# Gate_Driver.net
KiCad netlist of a schematic drawn in Altium Designer
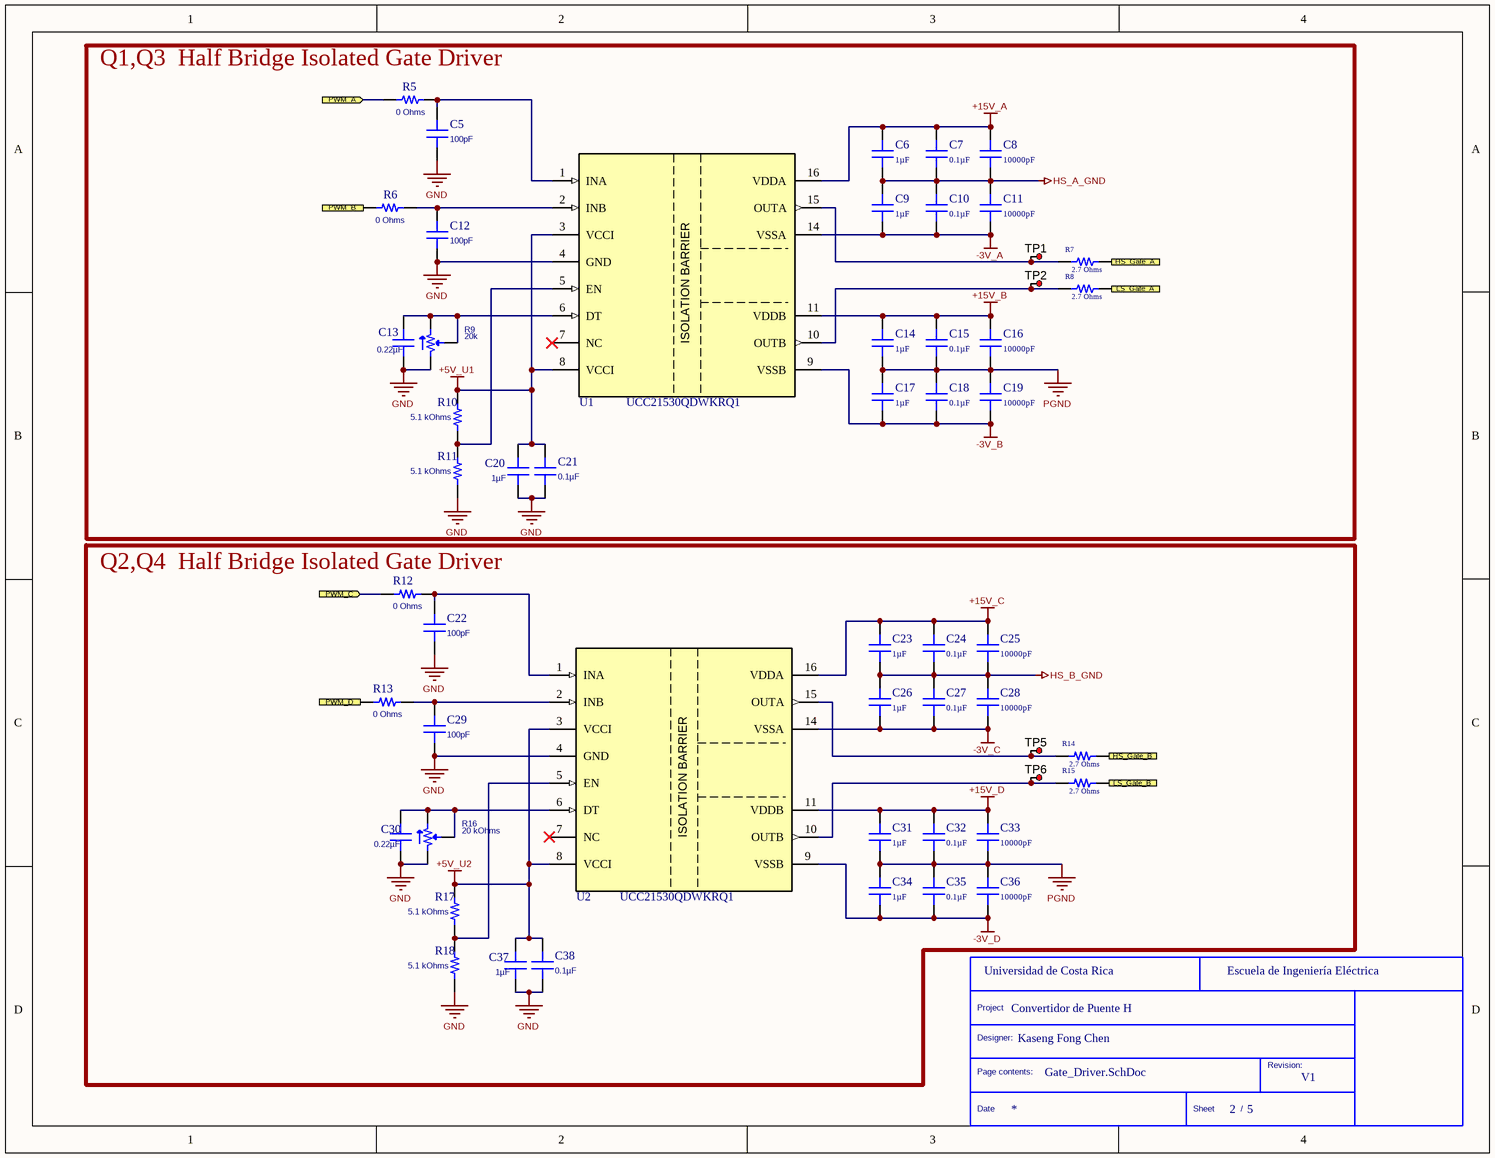
[diagram p0: Gate_Driver.SchDoc]

(export (version "E")
  (design (tool "Eeschema 10.0.6"))
  (components
    (comp (ref "C5")
      (value "100pF")
      (footprint "CAP 0603_1608")
      (description "CAP CER 100PF 100V C0G/NP0 0603")
      (fields
        (field (name "PART NUMBER") "GCM1885C2A101JA16D")
        (field (name "MANUFACTURER") "Murata Electronics")
      )
      (libsource (lib "Celestial Altium Library - altium_library") (part "Capacitor"))
    )
    (comp (ref "C6")
      (value "1µF")
      (footprint "CAP 0603_1608")
      (description "CAP CER 1UF 50V X7R 0603")
      (fields (field (name "PART NUMBER") "UMK107AB7105KA-T") (field (name "MANUFACTURER") "Taiyo Yuden"))
      (libsource (lib "Celestial Altium Library - altium_library") (part "Capacitor"))
    )
    (comp (ref "C7")
      (value "0.1µF")
      (footprint "CAP 0603_1608")
      (description "CAP CER 0.1UF 50V X7R 0603")
      (fields (field (name "PART NUMBER") "C0603C104M5RACTU") (field (name "MANUFACTURER") "KEMET"))
      (libsource (lib "Celestial Altium Library - altium_library") (part "Capacitor"))
    )
    (comp (ref "C8")
      (value "10000pF")
      (footprint "CAP 0603_1608")
      (description "CAP CER 10000PF 50V C0G 0603")
      (fields
        (field (name "PART NUMBER") "CGA3E2C0G1H103J080AA")
        (field (name "MANUFACTURER") "TDK Corporation")
      )
      (libsource (lib "Celestial Altium Library - altium_library") (part "Capacitor"))
    )
    (comp (ref "C9")
      (value "1µF")
      (footprint "CAP 0603_1608")
      (description "CAP CER 1UF 50V X7R 0603")
      (fields (field (name "PART NUMBER") "UMK107AB7105KA-T") (field (name "MANUFACTURER") "Taiyo Yuden"))
      (libsource (lib "Celestial Altium Library - altium_library") (part "Capacitor"))
    )
    (comp (ref "C10")
      (value "0.1µF")
      (footprint "CAP 0603_1608")
      (description "CAP CER 0.1UF 50V X7R 0603")
      (fields (field (name "PART NUMBER") "C0603C104M5RACTU") (field (name "MANUFACTURER") "KEMET"))
      (libsource (lib "Celestial Altium Library - altium_library") (part "Capacitor"))
    )
    (comp (ref "C11")
      (value "10000pF")
      (footprint "CAP 0603_1608")
      (description "CAP CER 10000PF 50V C0G 0603")
      (fields
        (field (name "PART NUMBER") "CGA3E2C0G1H103J080AA")
        (field (name "MANUFACTURER") "TDK Corporation")
      )
      (libsource (lib "Celestial Altium Library - altium_library") (part "Capacitor"))
    )
    (comp (ref "C12")
      (value "100pF")
      (footprint "CAP 0603_1608")
      (description "CAP CER 100PF 100V C0G/NP0 0603")
      (fields
        (field (name "PART NUMBER") "GCM1885C2A101JA16D")
        (field (name "MANUFACTURER") "Murata Electronics")
      )
      (libsource (lib "Celestial Altium Library - altium_library") (part "Capacitor"))
    )
    (comp (ref "C13")
      (value "0.22µF")
      (footprint "CAP 0603_1608")
      (description "CAP CER 0.22UF 25V X7R 0603")
      (fields
        (field (name "PART NUMBER") "GRM188R71E224KA88J")
        (field (name "MANUFACTURER") "Murata Electronics")
      )
      (libsource (lib "Celestial Altium Library - altium_library") (part "Capacitor"))
    )
    (comp (ref "C14")
      (value "1µF")
      (footprint "CAP 0603_1608")
      (description "CAP CER 1UF 50V X7R 0603")
      (fields (field (name "PART NUMBER") "UMK107AB7105KA-T") (field (name "MANUFACTURER") "Taiyo Yuden"))
      (libsource (lib "Celestial Altium Library - altium_library") (part "Capacitor"))
    )
    (comp (ref "C15")
      (value "0.1µF")
      (footprint "CAP 0603_1608")
      (description "CAP CER 0.1UF 50V X7R 0603")
      (fields (field (name "PART NUMBER") "C0603C104M5RACTU") (field (name "MANUFACTURER") "KEMET"))
      (libsource (lib "Celestial Altium Library - altium_library") (part "Capacitor"))
    )
    (comp (ref "C16")
      (value "10000pF")
      (footprint "CAP 0603_1608")
      (description "CAP CER 10000PF 50V C0G 0603")
      (fields
        (field (name "PART NUMBER") "CGA3E2C0G1H103J080AA")
        (field (name "MANUFACTURER") "TDK Corporation")
      )
      (libsource (lib "Celestial Altium Library - altium_library") (part "Capacitor"))
    )
    (comp (ref "C17")
      (value "1µF")
      (footprint "CAP 0603_1608")
      (description "CAP CER 1UF 50V X7R 0603")
      (fields (field (name "PART NUMBER") "UMK107AB7105KA-T") (field (name "MANUFACTURER") "Taiyo Yuden"))
      (libsource (lib "Celestial Altium Library - altium_library") (part "Capacitor"))
    )
    (comp (ref "C18")
      (value "0.1µF")
      (footprint "CAP 0603_1608")
      (description "CAP CER 0.1UF 50V X7R 0603")
      (fields (field (name "PART NUMBER") "C0603C104M5RACTU") (field (name "MANUFACTURER") "KEMET"))
      (libsource (lib "Celestial Altium Library - altium_library") (part "Capacitor"))
    )
    (comp (ref "C19")
      (value "10000pF")
      (footprint "CAP 0603_1608")
      (description "CAP CER 10000PF 50V C0G 0603")
      (fields
        (field (name "PART NUMBER") "CGA3E2C0G1H103J080AA")
        (field (name "MANUFACTURER") "TDK Corporation")
      )
      (libsource (lib "Celestial Altium Library - altium_library") (part "Capacitor"))
    )
    (comp (ref "C20")
      (value "1µF")
      (footprint "CAP 0603_1608")
      (description "CAP CER 1UF 50V X7R 0603")
      (fields (field (name "PART NUMBER") "UMK107AB7105KA-T") (field (name "MANUFACTURER") "Taiyo Yuden"))
      (libsource (lib "Celestial Altium Library - altium_library") (part "Capacitor"))
    )
    (comp (ref "C21")
      (value "0.1µF")
      (footprint "CAP 0603_1608")
      (description "CAP CER 0.1UF 25V X7R 0603")
      (fields
        (field (name "PART NUMBER") "CGA3E2X7R1E104K080AA")
        (field (name "MANUFACTURER") "TDK Corporation")
      )
      (libsource (lib "Celestial Altium Library - altium_library") (part "Capacitor"))
    )
    (comp (ref "C22")
      (value "100pF")
      (footprint "CAP 0603_1608")
      (description "CAP CER 100PF 100V C0G/NP0 0603")
      (fields
        (field (name "PART NUMBER") "GCM1885C2A101JA16D")
        (field (name "MANUFACTURER") "Murata Electronics")
      )
      (libsource (lib "Celestial Altium Library - altium_library") (part "Capacitor"))
    )
    (comp (ref "C23")
      (value "1µF")
      (footprint "CAP 0603_1608")
      (description "CAP CER 1UF 50V X7R 0603")
      (fields (field (name "PART NUMBER") "UMK107AB7105KA-T") (field (name "MANUFACTURER") "Taiyo Yuden"))
      (libsource (lib "Celestial Altium Library - altium_library") (part "Capacitor"))
    )
    (comp (ref "C24")
      (value "0.1µF")
      (footprint "CAP 0603_1608")
      (description "CAP CER 0.1UF 50V X7R 0603")
      (fields (field (name "PART NUMBER") "C0603C104M5RACTU") (field (name "MANUFACTURER") "KEMET"))
      (libsource (lib "Celestial Altium Library - altium_library") (part "Capacitor"))
    )
    (comp (ref "C25")
      (value "10000pF")
      (footprint "CAP 0603_1608")
      (description "CAP CER 10000PF 50V C0G 0603")
      (fields
        (field (name "PART NUMBER") "CGA3E2C0G1H103J080AA")
        (field (name "MANUFACTURER") "TDK Corporation")
      )
      (libsource (lib "Celestial Altium Library - altium_library") (part "Capacitor"))
    )
    (comp (ref "C26")
      (value "1µF")
      (footprint "CAP 0603_1608")
      (description "CAP CER 1UF 50V X7R 0603")
      (fields (field (name "PART NUMBER") "UMK107AB7105KA-T") (field (name "MANUFACTURER") "Taiyo Yuden"))
      (libsource (lib "Celestial Altium Library - altium_library") (part "Capacitor"))
    )
    (comp (ref "C27")
      (value "0.1µF")
      (footprint "CAP 0603_1608")
      (description "CAP CER 0.1UF 50V X7R 0603")
      (fields (field (name "PART NUMBER") "C0603C104M5RACTU") (field (name "MANUFACTURER") "KEMET"))
      (libsource (lib "Celestial Altium Library - altium_library") (part "Capacitor"))
    )
    (comp (ref "C28")
      (value "10000pF")
      (footprint "CAP 0603_1608")
      (description "CAP CER 10000PF 50V C0G 0603")
      (fields
        (field (name "PART NUMBER") "CGA3E2C0G1H103J080AA")
        (field (name "MANUFACTURER") "TDK Corporation")
      )
      (libsource (lib "Celestial Altium Library - altium_library") (part "Capacitor"))
    )
    (comp (ref "C29")
      (value "100pF")
      (footprint "CAP 0603_1608")
      (description "CAP CER 100PF 100V C0G/NP0 0603")
      (fields
        (field (name "PART NUMBER") "GCM1885C2A101JA16D")
        (field (name "MANUFACTURER") "Murata Electronics")
      )
      (libsource (lib "Celestial Altium Library - altium_library") (part "Capacitor"))
    )
    (comp (ref "C30")
      (value "0.22µF")
      (footprint "CAP 0603_1608")
      (description "CAP CER 0.22UF 25V X7R 0603")
      (fields
        (field (name "PART NUMBER") "GRM188R71E224KA88J")
        (field (name "MANUFACTURER") "Murata Electronics")
      )
      (libsource (lib "Celestial Altium Library - altium_library") (part "Capacitor"))
    )
    (comp (ref "C31")
      (value "1µF")
      (footprint "CAP 0603_1608")
      (description "CAP CER 1UF 50V X7R 0603")
      (fields (field (name "PART NUMBER") "UMK107AB7105KA-T") (field (name "MANUFACTURER") "Taiyo Yuden"))
      (libsource (lib "Celestial Altium Library - altium_library") (part "Capacitor"))
    )
    (comp (ref "C32")
      (value "0.1µF")
      (footprint "CAP 0603_1608")
      (description "CAP CER 0.1UF 50V X7R 0603")
      (fields (field (name "PART NUMBER") "C0603C104M5RACTU") (field (name "MANUFACTURER") "KEMET"))
      (libsource (lib "Celestial Altium Library - altium_library") (part "Capacitor"))
    )
    (comp (ref "C33")
      (value "10000pF")
      (footprint "CAP 0603_1608")
      (description "CAP CER 10000PF 50V C0G 0603")
      (fields
        (field (name "PART NUMBER") "CGA3E2C0G1H103J080AA")
        (field (name "MANUFACTURER") "TDK Corporation")
      )
      (libsource (lib "Celestial Altium Library - altium_library") (part "Capacitor"))
    )
    (comp (ref "C34")
      (value "1µF")
      (footprint "CAP 0603_1608")
      (description "CAP CER 1UF 50V X7R 0603")
      (fields (field (name "PART NUMBER") "UMK107AB7105KA-T") (field (name "MANUFACTURER") "Taiyo Yuden"))
      (libsource (lib "Celestial Altium Library - altium_library") (part "Capacitor"))
    )
    (comp (ref "C35")
      (value "0.1µF")
      (footprint "CAP 0603_1608")
      (description "CAP CER 0.1UF 50V X7R 0603")
      (fields (field (name "PART NUMBER") "C0603C104M5RACTU") (field (name "MANUFACTURER") "KEMET"))
      (libsource (lib "Celestial Altium Library - altium_library") (part "Capacitor"))
    )
    (comp (ref "C36")
      (value "10000pF")
      (footprint "CAP 0603_1608")
      (description "CAP CER 10000PF 50V C0G 0603")
      (fields
        (field (name "PART NUMBER") "CGA3E2C0G1H103J080AA")
        (field (name "MANUFACTURER") "TDK Corporation")
      )
      (libsource (lib "Celestial Altium Library - altium_library") (part "Capacitor"))
    )
    (comp (ref "C37")
      (value "1µF")
      (footprint "CAP 0603_1608")
      (description "CAP CER 1UF 50V X7R 0603")
      (fields (field (name "PART NUMBER") "UMK107AB7105KA-T") (field (name "MANUFACTURER") "Taiyo Yuden"))
      (libsource (lib "Celestial Altium Library - altium_library") (part "Capacitor"))
    )
    (comp (ref "C38")
      (value "0.1µF")
      (footprint "CAP 0603_1608")
      (description "CAP CER 0.1UF 25V X7R 0603")
      (fields
        (field (name "PART NUMBER") "CGA3E2X7R1E104K080AA")
        (field (name "MANUFACTURER") "TDK Corporation")
      )
      (libsource (lib "Celestial Altium Library - altium_library") (part "Capacitor"))
    )
    (comp (ref "R5")
      (value "0 Ohms")
      (footprint "RES 0603_1608")
      (description "RES SMD 0 OHM JUMPER 1/4W 0603")
      (fields (field (name "PART NUMBER") "CRCW06030000Z0EAHP") (field (name "MANUFACTURER") "Vishay Dale"))
      (libsource (lib "Celestial Altium Library - altium_library") (part "Resistor"))
    )
    (comp (ref "R6")
      (value "0 Ohms")
      (footprint "RES 0603_1608")
      (description "RES SMD 0 OHM JUMPER 1/4W 0603")
      (fields (field (name "PART NUMBER") "CRCW06030000Z0EAHP") (field (name "MANUFACTURER") "Vishay Dale"))
      (libsource (lib "Celestial Altium Library - altium_library") (part "Resistor"))
    )
    (comp (ref "R7")
      (value "2.7 Ohms")
      (footprint "RES 1206_3216")
      (description "RES SMD 2.7 OHM 1% 3/4W 1206")
      (fields (field (name "PART NUMBER") "CRCW12062R70FKEAHP") (field (name "MANUFACTURER") "Vishay Dale"))
      (libsource (lib "Celestial Altium Library - altium_library") (part "Resistor"))
    )
    (comp (ref "R8")
      (value "2.7 Ohms")
      (footprint "RES 1206_3216")
      (description "RES SMD 2.7 OHM 1% 3/4W 1206")
      (fields (field (name "PART NUMBER") "CRCW12062R70FKEAHP") (field (name "MANUFACTURER") "Vishay Dale"))
      (libsource (lib "Celestial Altium Library - altium_library") (part "Resistor"))
    )
    (comp (ref "R9")
      (value "20k")
      (footprint "POT BOURNS TRIMPOT TC33")
      (description "TRIMMER 20K OHM 0.1W J LEAD TOP")
      (fields (field (name "PART NUMBER") "TC33X-2-203E") (field (name "MANUFACTURER") "Bourns Inc."))
      (libsource (lib "Celestial Altium Library - altium_library") (part "Potentiometer"))
    )
    (comp (ref "R10")
      (value "5.1 kOhms")
      (footprint "RES 0603_1608")
      (description "RES SMD 5.1K OHM 5% 1/10W 0603")
      (fields (field (name "PART NUMBER") "RC0603JR-075K1L") (field (name "MANUFACTURER") "Yageo"))
      (libsource (lib "Celestial Altium Library - altium_library") (part "Resistor"))
    )
    (comp (ref "R11")
      (value "5.1 kOhms")
      (footprint "RES 0603_1608")
      (description "RES SMD 5.1K OHM 5% 1/10W 0603")
      (fields (field (name "PART NUMBER") "RC0603JR-075K1L") (field (name "MANUFACTURER") "Yageo"))
      (libsource (lib "Celestial Altium Library - altium_library") (part "Resistor"))
    )
    (comp (ref "R12")
      (value "0 Ohms")
      (footprint "RES 0603_1608")
      (description "RES SMD 0 OHM JUMPER 1/4W 0603")
      (fields (field (name "PART NUMBER") "CRCW06030000Z0EAHP") (field (name "MANUFACTURER") "Vishay Dale"))
      (libsource (lib "Celestial Altium Library - altium_library") (part "Resistor"))
    )
    (comp (ref "R13")
      (value "0 Ohms")
      (footprint "RES 0603_1608")
      (description "RES SMD 0 OHM JUMPER 1/4W 0603")
      (fields (field (name "PART NUMBER") "CRCW06030000Z0EAHP") (field (name "MANUFACTURER") "Vishay Dale"))
      (libsource (lib "Celestial Altium Library - altium_library") (part "Resistor"))
    )
    (comp (ref "R14")
      (value "2.7 Ohms")
      (footprint "RES 1206_3216")
      (description "RES SMD 2.7 OHM 1% 3/4W 1206")
      (fields (field (name "PART NUMBER") "CRCW12062R70FKEAHP") (field (name "MANUFACTURER") "Vishay Dale"))
      (libsource (lib "Celestial Altium Library - altium_library") (part "Resistor"))
    )
    (comp (ref "R15")
      (value "2.7 Ohms")
      (footprint "RES 1206_3216")
      (description "RES SMD 2.7 OHM 1% 3/4W 1206")
      (fields (field (name "PART NUMBER") "CRCW12062R70FKEAHP") (field (name "MANUFACTURER") "Vishay Dale"))
      (libsource (lib "Celestial Altium Library - altium_library") (part "Resistor"))
    )
    (comp (ref "R16")
      (value "20 kOhms")
      (footprint "POT BOURNS TRIMPOT TC33")
      (description "TRIMMER 20K OHM 0.1W J LEAD TOP")
      (fields (field (name "PART NUMBER") "TC33X-2-203E") (field (name "MANUFACTURER") "Bourns Inc."))
      (libsource (lib "Celestial Altium Library - altium_library") (part "Potentiometer"))
    )
    (comp (ref "R17")
      (value "5.1 kOhms")
      (footprint "RES 0603_1608")
      (description "RES SMD 5.1K OHM 5% 1/10W 0603")
      (fields (field (name "PART NUMBER") "RC0603JR-075K1L") (field (name "MANUFACTURER") "Yageo"))
      (libsource (lib "Celestial Altium Library - altium_library") (part "Resistor"))
    )
    (comp (ref "R18")
      (value "5.1 kOhms")
      (footprint "RES 0603_1608")
      (description "RES SMD 5.1K OHM 5% 1/10W 0603")
      (fields (field (name "PART NUMBER") "RC0603JR-075K1L") (field (name "MANUFACTURER") "Yageo"))
      (libsource (lib "Celestial Altium Library - altium_library") (part "Resistor"))
    )
    (comp (ref "TP1")
      (value "5010")
      (footprint "Keystone5010")
      (description "Test Point, Multipurpose, Red, TH")
      (fields (field (name "MANUFACTURER") "Keystone") (field (name "PUBLISHER") "Texas Instruments"))
      (libsource (lib "kasengLib") (part "5010"))
    )
    (comp (ref "TP2")
      (value "5010")
      (footprint "Keystone5010")
      (description "Test Point, Multipurpose, Red, TH")
      (fields (field (name "MANUFACTURER") "Keystone") (field (name "PUBLISHER") "Texas Instruments"))
      (libsource (lib "kasengLib") (part "5010"))
    )
    (comp (ref "TP5")
      (value "5010")
      (footprint "Keystone5010")
      (description "Test Point, Multipurpose, Red, TH")
      (fields (field (name "MANUFACTURER") "Keystone") (field (name "PUBLISHER") "Texas Instruments"))
      (libsource (lib "kasengLib") (part "5010"))
    )
    (comp (ref "TP6")
      (value "5010")
      (footprint "Keystone5010")
      (description "Test Point, Multipurpose, Red, TH")
      (fields (field (name "MANUFACTURER") "Keystone") (field (name "PUBLISHER") "Texas Instruments"))
      (libsource (lib "kasengLib") (part "5010"))
    )
    (comp (ref "U1")
      (value "UCC21530QDWKRQ1")
      (footprint "DW0016B_HV")
      (description "Isolated Dual-Channel Gate Driver 6A 2-Output High Side/Low Side/Half-Bridge 14-Pin SOIC T/R")
      (fields (field (name "MANUFACTURER") "Texas Instruments"))
      (libsource (lib "KasengLIb") (part "UCC21530QDWKRQ1 (2)"))
    )
    (comp (ref "U2")
      (value "UCC21530QDWKRQ1")
      (footprint "DW0016B_HV")
      (description "Isolated Dual-Channel Gate Driver 6A 2-Output High Side/Low Side/Half-Bridge 14-Pin SOIC T/R")
      (fields (field (name "MANUFACTURER") "Texas Instruments"))
      (libsource (lib "KasengLIb") (part "UCC21530QDWKRQ1 (2)"))
    )
  )
  (nets
    (net (code "1") (name "+5V_U1") (class "Default")
      (node (ref "C20") (pin "2") (pinfunction "2_2") (pintype "passive"))
      (node (ref "C21") (pin "2") (pinfunction "2_2") (pintype "passive"))
      (node (ref "R10") (pin "2") (pinfunction "2_2") (pintype "passive"))
      (node (ref "U1") (pin "3") (pinfunction "VCCI_3") (pintype "passive"))
      (node (ref "U1") (pin "8") (pinfunction "VCCI_8") (pintype "passive"))
    )
    (net (code "2") (name "+5V_U2") (class "Default")
      (node (ref "C37") (pin "2") (pinfunction "2_2") (pintype "passive"))
      (node (ref "C38") (pin "2") (pinfunction "2_2") (pintype "passive"))
      (node (ref "R17") (pin "2") (pinfunction "2_2") (pintype "passive"))
      (node (ref "U2") (pin "3") (pinfunction "VCCI_3") (pintype "passive"))
      (node (ref "U2") (pin "8") (pinfunction "VCCI_8") (pintype "passive"))
    )
    (net (code "3") (name "+15V_A") (class "Default")
      (node (ref "C6") (pin "2") (pinfunction "2_2") (pintype "passive"))
      (node (ref "C7") (pin "2") (pinfunction "2_2") (pintype "passive"))
      (node (ref "C8") (pin "2") (pinfunction "2_2") (pintype "passive"))
      (node (ref "U1") (pin "16") (pinfunction "VDDA_16") (pintype "passive"))
    )
    (net (code "4") (name "+15V_B") (class "Default")
      (node (ref "C14") (pin "2") (pinfunction "2_2") (pintype "passive"))
      (node (ref "C15") (pin "2") (pinfunction "2_2") (pintype "passive"))
      (node (ref "C16") (pin "2") (pinfunction "2_2") (pintype "passive"))
      (node (ref "U1") (pin "11") (pinfunction "VDDB_11") (pintype "passive"))
    )
    (net (code "5") (name "+15V_C") (class "Default")
      (node (ref "C23") (pin "2") (pinfunction "2_2") (pintype "passive"))
      (node (ref "C24") (pin "2") (pinfunction "2_2") (pintype "passive"))
      (node (ref "C25") (pin "2") (pinfunction "2_2") (pintype "passive"))
      (node (ref "U2") (pin "16") (pinfunction "VDDA_16") (pintype "passive"))
    )
    (net (code "6") (name "+15V_D") (class "Default")
      (node (ref "C31") (pin "2") (pinfunction "2_2") (pintype "passive"))
      (node (ref "C32") (pin "2") (pinfunction "2_2") (pintype "passive"))
      (node (ref "C33") (pin "2") (pinfunction "2_2") (pintype "passive"))
      (node (ref "U2") (pin "11") (pinfunction "VDDB_11") (pintype "passive"))
    )
    (net (code "7") (name "-3V_A") (class "Default")
      (node (ref "C10") (pin "1") (pinfunction "1_1") (pintype "passive"))
      (node (ref "C11") (pin "1") (pinfunction "1_1") (pintype "passive"))
      (node (ref "C9") (pin "1") (pinfunction "1_1") (pintype "passive"))
      (node (ref "U1") (pin "14") (pinfunction "VSSA_14") (pintype "passive"))
    )
    (net (code "8") (name "-3V_B") (class "Default")
      (node (ref "C17") (pin "1") (pinfunction "1_1") (pintype "passive"))
      (node (ref "C18") (pin "1") (pinfunction "1_1") (pintype "passive"))
      (node (ref "C19") (pin "1") (pinfunction "1_1") (pintype "passive"))
      (node (ref "U1") (pin "9") (pinfunction "VSSB_9") (pintype "passive"))
    )
    (net (code "9") (name "-3V_C") (class "Default")
      (node (ref "C26") (pin "1") (pinfunction "1_1") (pintype "passive"))
      (node (ref "C27") (pin "1") (pinfunction "1_1") (pintype "passive"))
      (node (ref "C28") (pin "1") (pinfunction "1_1") (pintype "passive"))
      (node (ref "U2") (pin "14") (pinfunction "VSSA_14") (pintype "passive"))
    )
    (net (code "10") (name "-3V_D") (class "Default")
      (node (ref "C34") (pin "1") (pinfunction "1_1") (pintype "passive"))
      (node (ref "C35") (pin "1") (pinfunction "1_1") (pintype "passive"))
      (node (ref "C36") (pin "1") (pinfunction "1_1") (pintype "passive"))
      (node (ref "U2") (pin "9") (pinfunction "VSSB_9") (pintype "passive"))
    )
    (net (code "11") (name "/HS_Gate_A") (class "Default")
      (node (ref "R7") (pin "2") (pinfunction "2_2") (pintype "passive"))
    )
    (net (code "12") (name "/HS_Gate_B") (class "Default")
      (node (ref "R14") (pin "2") (pinfunction "2_2") (pintype "passive"))
    )
    (net (code "13") (name "/LS_Gate_A") (class "Default")
      (node (ref "R8") (pin "2") (pinfunction "2_2") (pintype "passive"))
    )
    (net (code "14") (name "/LS_Gate_B") (class "Default")
      (node (ref "R15") (pin "2") (pinfunction "2_2") (pintype "passive"))
    )
    (net (code "15") (name "/PWM_A") (class "Default")
      (node (ref "R5") (pin "1") (pinfunction "1_1") (pintype "passive"))
    )
    (net (code "16") (name "/PWM_B") (class "Default")
      (node (ref "R6") (pin "1") (pinfunction "1_1") (pintype "passive"))
    )
    (net (code "17") (name "/PWM_C") (class "Default")
      (node (ref "R12") (pin "1") (pinfunction "1_1") (pintype "passive"))
    )
    (net (code "18") (name "/PWM_D") (class "Default")
      (node (ref "R13") (pin "1") (pinfunction "1_1") (pintype "passive"))
    )
    (net (code "19") (name "GND") (class "Default")
      (node (ref "C12") (pin "1") (pinfunction "1_1") (pintype "passive"))
      (node (ref "C13") (pin "1") (pinfunction "1_1") (pintype "passive"))
      (node (ref "C20") (pin "1") (pinfunction "1_1") (pintype "passive"))
      (node (ref "C21") (pin "1") (pinfunction "1_1") (pintype "passive"))
      (node (ref "C22") (pin "1") (pinfunction "1_1") (pintype "passive"))
      (node (ref "C29") (pin "1") (pinfunction "1_1") (pintype "passive"))
      (node (ref "C30") (pin "1") (pinfunction "1_1") (pintype "passive"))
      (node (ref "C37") (pin "1") (pinfunction "1_1") (pintype "passive"))
      (node (ref "C38") (pin "1") (pinfunction "1_1") (pintype "passive"))
      (node (ref "C5") (pin "1") (pinfunction "1_1") (pintype "passive"))
      (node (ref "R11") (pin "1") (pinfunction "1_1") (pintype "passive"))
      (node (ref "R16") (pin "1") (pinfunction "1_1") (pintype "passive"))
      (node (ref "R18") (pin "1") (pinfunction "1_1") (pintype "passive"))
      (node (ref "R9") (pin "1") (pinfunction "1_1") (pintype "passive"))
      (node (ref "U1") (pin "4") (pinfunction "GND_4") (pintype "power_in"))
      (node (ref "U2") (pin "4") (pinfunction "GND_4") (pintype "power_in"))
    )
    (net (code "20") (name "HS_A_GND") (class "Default")
      (node (ref "C10") (pin "2") (pinfunction "2_2") (pintype "passive"))
      (node (ref "C11") (pin "2") (pinfunction "2_2") (pintype "passive"))
      (node (ref "C6") (pin "1") (pinfunction "1_1") (pintype "passive"))
      (node (ref "C7") (pin "1") (pinfunction "1_1") (pintype "passive"))
      (node (ref "C8") (pin "1") (pinfunction "1_1") (pintype "passive"))
      (node (ref "C9") (pin "2") (pinfunction "2_2") (pintype "passive"))
    )
    (net (code "21") (name "HS_B_GND") (class "Default")
      (node (ref "C23") (pin "1") (pinfunction "1_1") (pintype "passive"))
      (node (ref "C24") (pin "1") (pinfunction "1_1") (pintype "passive"))
      (node (ref "C25") (pin "1") (pinfunction "1_1") (pintype "passive"))
      (node (ref "C26") (pin "2") (pinfunction "2_2") (pintype "passive"))
      (node (ref "C27") (pin "2") (pinfunction "2_2") (pintype "passive"))
      (node (ref "C28") (pin "2") (pinfunction "2_2") (pintype "passive"))
    )
    (net (code "22") (name "Net-(U1-DT)") (class "Default")
      (node (ref "C13") (pin "2") (pinfunction "2_2") (pintype "passive"))
      (node (ref "R9") (pin "2") (pinfunction "2_2") (pintype "passive"))
      (node (ref "R9") (pin "3") (pinfunction "3_3") (pintype "passive"))
      (node (ref "U1") (pin "6") (pinfunction "DT_6") (pintype "input"))
    )
    (net (code "23") (name "Net-(U1-EN)") (class "Default")
      (node (ref "R10") (pin "1") (pinfunction "1_1") (pintype "passive"))
      (node (ref "R11") (pin "2") (pinfunction "2_2") (pintype "passive"))
      (node (ref "U1") (pin "5") (pinfunction "EN_5") (pintype "input"))
    )
    (net (code "24") (name "Net-(U1-INA)") (class "Default")
      (node (ref "C5") (pin "2") (pinfunction "2_2") (pintype "passive"))
      (node (ref "R5") (pin "2") (pinfunction "2_2") (pintype "passive"))
      (node (ref "U1") (pin "1") (pinfunction "INA_1") (pintype "input"))
    )
    (net (code "25") (name "Net-(U1-INB)") (class "Default")
      (node (ref "C12") (pin "2") (pinfunction "2_2") (pintype "passive"))
      (node (ref "R6") (pin "2") (pinfunction "2_2") (pintype "passive"))
      (node (ref "U1") (pin "2") (pinfunction "INB_2") (pintype "input"))
    )
    (net (code "26") (name "Net-(U1-OUTA)") (class "Default")
      (node (ref "R7") (pin "1") (pinfunction "1_1") (pintype "passive"))
      (node (ref "TP1") (pin "1") (pinfunction "1_1") (pintype "passive"))
      (node (ref "U1") (pin "15") (pinfunction "OUTA_15") (pintype "output"))
    )
    (net (code "27") (name "Net-(U1-OUTB)") (class "Default")
      (node (ref "R8") (pin "1") (pinfunction "1_1") (pintype "passive"))
      (node (ref "TP2") (pin "1") (pinfunction "1_1") (pintype "passive"))
      (node (ref "U1") (pin "10") (pinfunction "OUTB_10") (pintype "output"))
    )
    (net (code "28") (name "Net-(U2-DT)") (class "Default")
      (node (ref "C30") (pin "2") (pinfunction "2_2") (pintype "passive"))
      (node (ref "R16") (pin "2") (pinfunction "2_2") (pintype "passive"))
      (node (ref "R16") (pin "3") (pinfunction "3_3") (pintype "passive"))
      (node (ref "U2") (pin "6") (pinfunction "DT_6") (pintype "input"))
    )
    (net (code "29") (name "Net-(U2-EN)") (class "Default")
      (node (ref "R17") (pin "1") (pinfunction "1_1") (pintype "passive"))
      (node (ref "R18") (pin "2") (pinfunction "2_2") (pintype "passive"))
      (node (ref "U2") (pin "5") (pinfunction "EN_5") (pintype "input"))
    )
    (net (code "30") (name "Net-(U2-INA)") (class "Default")
      (node (ref "C22") (pin "2") (pinfunction "2_2") (pintype "passive"))
      (node (ref "R12") (pin "2") (pinfunction "2_2") (pintype "passive"))
      (node (ref "U2") (pin "1") (pinfunction "INA_1") (pintype "input"))
    )
    (net (code "31") (name "Net-(U2-INB)") (class "Default")
      (node (ref "C29") (pin "2") (pinfunction "2_2") (pintype "passive"))
      (node (ref "R13") (pin "2") (pinfunction "2_2") (pintype "passive"))
      (node (ref "U2") (pin "2") (pinfunction "INB_2") (pintype "input"))
    )
    (net (code "32") (name "Net-(U2-OUTA)") (class "Default")
      (node (ref "R14") (pin "1") (pinfunction "1_1") (pintype "passive"))
      (node (ref "TP5") (pin "1") (pinfunction "1_1") (pintype "passive"))
      (node (ref "U2") (pin "15") (pinfunction "OUTA_15") (pintype "output"))
    )
    (net (code "33") (name "Net-(U2-OUTB)") (class "Default")
      (node (ref "R15") (pin "1") (pinfunction "1_1") (pintype "passive"))
      (node (ref "TP6") (pin "1") (pinfunction "1_1") (pintype "passive"))
      (node (ref "U2") (pin "10") (pinfunction "OUTB_10") (pintype "output"))
    )
    (net (code "34") (name "PGND") (class "Default")
      (node (ref "C14") (pin "1") (pinfunction "1_1") (pintype "passive"))
      (node (ref "C15") (pin "1") (pinfunction "1_1") (pintype "passive"))
      (node (ref "C16") (pin "1") (pinfunction "1_1") (pintype "passive"))
      (node (ref "C17") (pin "2") (pinfunction "2_2") (pintype "passive"))
      (node (ref "C18") (pin "2") (pinfunction "2_2") (pintype "passive"))
      (node (ref "C19") (pin "2") (pinfunction "2_2") (pintype "passive"))
      (node (ref "C31") (pin "1") (pinfunction "1_1") (pintype "passive"))
      (node (ref "C32") (pin "1") (pinfunction "1_1") (pintype "passive"))
      (node (ref "C33") (pin "1") (pinfunction "1_1") (pintype "passive"))
      (node (ref "C34") (pin "2") (pinfunction "2_2") (pintype "passive"))
      (node (ref "C35") (pin "2") (pinfunction "2_2") (pintype "passive"))
      (node (ref "C36") (pin "2") (pinfunction "2_2") (pintype "passive"))
    )
    (net (code "35") (name "unconnected-(U1-NC-Pad7)") (class "Default")
      (node (ref "U1") (pin "7") (pinfunction "NC_7") (pintype "passive+no_connect"))
    )
    (net (code "36") (name "unconnected-(U2-NC-Pad7)") (class "Default")
      (node (ref "U2") (pin "7") (pinfunction "NC_7") (pintype "passive+no_connect"))
    )
  )
)
